# 05_-POWER.net
KiCad netlist of a schematic drawn in Altium Designer
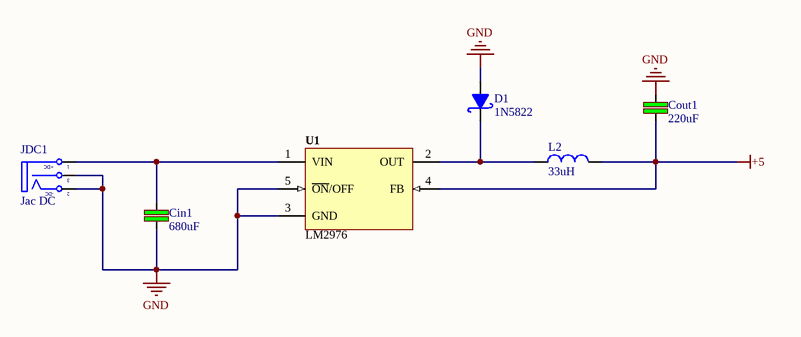
[diagram p0: [05]-POWER.SchDoc]

(export (version "E")
  (design (tool "Eeschema 10.0.6"))
  (components
    (comp (ref "Cin1")
      (value "680uF")
      (footprint "CAP_D10")
      (description "Cap SMD")
      (libsource (lib "My Library") (part "C"))
    )
    (comp (ref "Cout1")
      (value "220uF")
      (footprint "CAP_D10")
      (description "Cap SMD")
      (libsource (lib "My Library") (part "C"))
    )
    (comp (ref "D1")
      (value "1N5822")
      (footprint "SMA")
      (description "Schottky Rectifiers")
      (libsource (lib "My Library") (part "1N5822"))
    )
    (comp (ref "JDC1")
      (value "Jac DC")
      (footprint "DC-IN")
      (description "Jac DC input")
      (libsource (lib "My Library") (part "DCIN"))
    )
    (comp (ref "L2")
      (value "33uH")
      (footprint "L-SMD-M-7.3x4.5")
      (description "Inductor")
      (libsource (lib "My Library") (part "L1"))
    )
    (comp (ref "U1") (value "LM2976") (footprint "TO-263") (libsource (lib "My Library") (part "LM2596")))
  )
  (nets
    (net (code "1") (name "+5") (class "Default")
      (node (ref "Cout1") (pin "2") (pinfunction "2_2") (pintype "passive"))
      (node (ref "L2") (pin "2") (pinfunction "2_2") (pintype "passive"))
      (node (ref "U1") (pin "4") (pinfunction "FB_4") (pintype "input"))
    )
    (net (code "2") (name "GND") (class "Default")
      (node (ref "Cin1") (pin "2") (pinfunction "2_2") (pintype "passive"))
      (node (ref "Cout1") (pin "1") (pinfunction "1_1") (pintype "passive"))
      (node (ref "D1") (pin "1") (pinfunction "A_1") (pintype "passive"))
      (node (ref "JDC1") (pin "2") (pinfunction "TN_2") (pintype "passive"))
      (node (ref "JDC1") (pin "3") (pinfunction "S_3") (pintype "power_in"))
      (node (ref "U1") (pin "3") (pinfunction "GND_3") (pintype "power_in"))
      (node (ref "U1") (pin "5") (pinfunction "~{ON}/OFF_5") (pintype "input"))
    )
    (net (code "3") (name "Net-(D1-K)") (class "Default")
      (node (ref "D1") (pin "2") (pinfunction "K_2") (pintype "passive"))
      (node (ref "L2") (pin "1") (pinfunction "1_1") (pintype "passive"))
      (node (ref "U1") (pin "2") (pinfunction "OUT_2") (pintype "power_in"))
    )
    (net (code "4") (name "Net-(JDC1-T)") (class "Default")
      (node (ref "Cin1") (pin "1") (pinfunction "1_1") (pintype "passive"))
      (node (ref "JDC1") (pin "1") (pinfunction "T_1") (pintype "passive"))
      (node (ref "U1") (pin "1") (pinfunction "VIN_1") (pintype "power_in"))
    )
  )
)
